# LimaIO.net
KiCad netlist of a schematic drawn in EAGLE
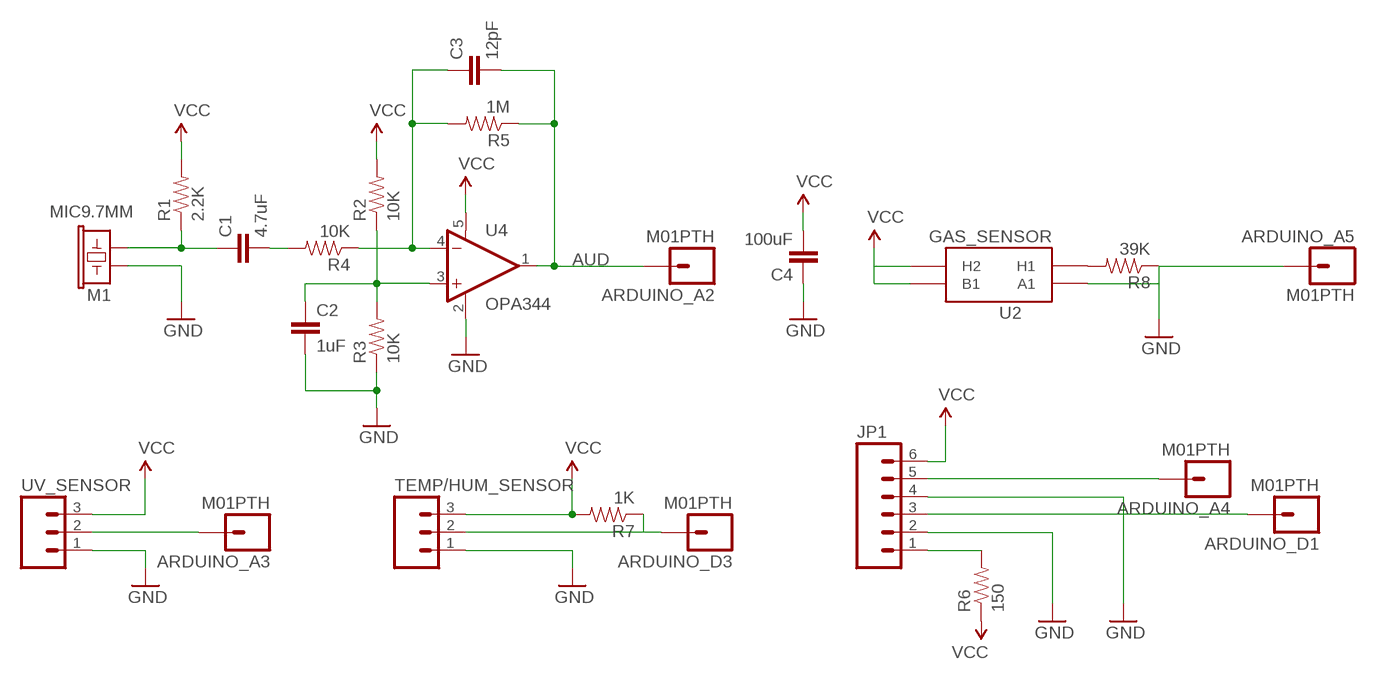
[diagram p0: schematic, sheet 1]

(export (version "E")
  (design (tool "Eeschema 10.0.6"))
  (components
    (comp (ref "ARDUINO_A2")
      (value "M01PTH")
      (footprint "eagle-import:1X01")
      (libsource (lib "eagle-import") (part "M01PTH"))
    )
    (comp (ref "ARDUINO_A3")
      (value "M01PTH")
      (footprint "eagle-import:1X01")
      (libsource (lib "eagle-import") (part "M01PTH"))
    )
    (comp (ref "ARDUINO_A4")
      (value "M01PTH")
      (footprint "eagle-import:1X01")
      (libsource (lib "eagle-import") (part "M01PTH"))
    )
    (comp (ref "ARDUINO_A5")
      (value "M01PTH")
      (footprint "eagle-import:1X01")
      (libsource (lib "eagle-import") (part "M01PTH"))
    )
    (comp (ref "ARDUINO_D1")
      (value "M01PTH")
      (footprint "eagle-import:1X01")
      (libsource (lib "eagle-import") (part "M01PTH"))
    )
    (comp (ref "ARDUINO_D3")
      (value "M01PTH")
      (footprint "eagle-import:1X01")
      (libsource (lib "eagle-import") (part "M01PTH"))
    )
    (comp (ref "C1")
      (value "4.7uF")
      (footprint "eagle-import:0402-CAP")
      (libsource (lib "eagle-import") (part "CAP0402-CAP"))
    )
    (comp (ref "C2")
      (value "1uF")
      (footprint "eagle-import:0402-CAP")
      (libsource (lib "eagle-import") (part "CAP0402-CAP"))
    )
    (comp (ref "C3")
      (value "12pF")
      (footprint "eagle-import:0402-CAP")
      (libsource (lib "eagle-import") (part "CAP0402-CAP"))
    )
    (comp (ref "C4")
      (value "100uF")
      (footprint "eagle-import:0402-CAP")
      (libsource (lib "eagle-import") (part "CAP0402-CAP"))
    )
    (comp (ref "JP1")
      (value "M06LONGPADS")
      (footprint "eagle-import:1X06_LONGPADS")
      (libsource (lib "eagle-import") (part "M06LONGPADS"))
    )
    (comp (ref "M1")
      (value "MIC9.7MM")
      (footprint "eagle-import:MIC-9.7MM")
      (libsource (lib "eagle-import") (part "MIC9.7MM"))
    )
    (comp (ref "R1")
      (value "2.2K")
      (footprint "eagle-import:0402-RES")
      (libsource (lib "eagle-import") (part "RESISTOR0402-RES"))
    )
    (comp (ref "R2")
      (value "10K")
      (footprint "eagle-import:0402-RES")
      (libsource (lib "eagle-import") (part "RESISTOR0402-RES"))
    )
    (comp (ref "R3")
      (value "10K")
      (footprint "eagle-import:0402-RES")
      (libsource (lib "eagle-import") (part "RESISTOR0402-RES"))
    )
    (comp (ref "R4")
      (value "10K")
      (footprint "eagle-import:0402-RES")
      (libsource (lib "eagle-import") (part "RESISTOR0402-RES"))
    )
    (comp (ref "R5")
      (value "1M")
      (footprint "eagle-import:0402-RES")
      (libsource (lib "eagle-import") (part "RESISTOR0402-RES"))
    )
    (comp (ref "R6")
      (value "150")
      (footprint "eagle-import:0402-RES")
      (libsource (lib "eagle-import") (part "RESISTOR0402-RES"))
    )
    (comp (ref "R7")
      (value "1K")
      (footprint "eagle-import:0402-RES")
      (libsource (lib "eagle-import") (part "RESISTOR0402-RES"))
    )
    (comp (ref "R8")
      (value "39K")
      (footprint "eagle-import:0402-RES")
      (libsource (lib "eagle-import") (part "RESISTOR0402-RES"))
    )
    (comp (ref "TEMP/HUM_SENSOR")
      (value "M03PTH")
      (footprint "eagle-import:1X03")
      (libsource (lib "eagle-import") (part "M03PTH"))
    )
    (comp (ref "U2")
      (value "GAS_SENSOR")
      (footprint "eagle-import:MQ-3")
      (libsource (lib "eagle-import") (part "GAS_SENSOR"))
    )
    (comp (ref "U4")
      (value "OPA344")
      (footprint "eagle-import:SOT23-5")
      (libsource (lib "eagle-import") (part "OPA344"))
    )
    (comp (ref "UV_SENSOR")
      (value "M03PTH")
      (footprint "eagle-import:1X03")
      (libsource (lib "eagle-import") (part "M03PTH"))
    )
  )
  (nets
    (net (code "1") (name "/AUD") (class "Default")
      (node (ref "ARDUINO_A2") (pin "1") (pinfunction "1_1") (pintype "passive"))
      (node (ref "C3") (pin "2") (pinfunction "2_2") (pintype "passive"))
      (node (ref "R5") (pin "1") (pinfunction "1_1") (pintype "passive"))
      (node (ref "U4") (pin "1") (pinfunction "OUT_1") (pintype "output"))
    )
    (net (code "2") (name "GND") (class "Default")
      (node (ref "ARDUINO_A5") (pin "1") (pinfunction "1_1") (pintype "passive"))
      (node (ref "C2") (pin "2") (pinfunction "2_2") (pintype "passive"))
      (node (ref "C4") (pin "1") (pinfunction "1_1") (pintype "passive"))
      (node (ref "JP1") (pin "2") (pinfunction "2_2") (pintype "passive"))
      (node (ref "JP1") (pin "4") (pinfunction "4_4") (pintype "passive"))
      (node (ref "M1") (pin "2") (pinfunction "2_2") (pintype "passive"))
      (node (ref "R3") (pin "1") (pinfunction "1_1") (pintype "passive"))
      (node (ref "R8") (pin "1") (pinfunction "1_1") (pintype "passive"))
      (node (ref "TEMP/HUM_SENSOR") (pin "1") (pinfunction "1_1") (pintype "passive"))
      (node (ref "U2") (pin "A1") (pinfunction "A1_A1") (pintype "bidirectional"))
      (node (ref "U4") (pin "2") (pinfunction "V-_2") (pintype "power_in"))
      (node (ref "UV_SENSOR") (pin "1") (pinfunction "1_1") (pintype "passive"))
    )
    (net (code "3") (name "Net-(ARDUINO_A3-Pad1)") (class "Default")
      (node (ref "ARDUINO_A3") (pin "1") (pinfunction "1_1") (pintype "passive"))
      (node (ref "UV_SENSOR") (pin "2") (pinfunction "2_2") (pintype "passive"))
    )
    (net (code "4") (name "Net-(ARDUINO_A4-Pad1)") (class "Default")
      (node (ref "ARDUINO_A4") (pin "1") (pinfunction "1_1") (pintype "passive"))
      (node (ref "JP1") (pin "5") (pinfunction "5_5") (pintype "passive"))
    )
    (net (code "5") (name "Net-(ARDUINO_D1-Pad1)") (class "Default")
      (node (ref "ARDUINO_D1") (pin "1") (pinfunction "1_1") (pintype "passive"))
      (node (ref "JP1") (pin "3") (pinfunction "3_3") (pintype "passive"))
    )
    (net (code "6") (name "Net-(ARDUINO_D3-Pad1)") (class "Default")
      (node (ref "ARDUINO_D3") (pin "1") (pinfunction "1_1") (pintype "passive"))
      (node (ref "R7") (pin "1") (pinfunction "1_1") (pintype "passive"))
      (node (ref "TEMP/HUM_SENSOR") (pin "2") (pinfunction "2_2") (pintype "passive"))
    )
    (net (code "7") (name "Net-(C1-Pad1)") (class "Default")
      (node (ref "C1") (pin "1") (pinfunction "1_1") (pintype "passive"))
      (node (ref "M1") (pin "1") (pinfunction "1_1") (pintype "passive"))
      (node (ref "R1") (pin "1") (pinfunction "1_1") (pintype "passive"))
    )
    (net (code "8") (name "Net-(C1-Pad2)") (class "Default")
      (node (ref "C1") (pin "2") (pinfunction "2_2") (pintype "passive"))
      (node (ref "R4") (pin "2") (pinfunction "2_2") (pintype "passive"))
    )
    (net (code "9") (name "Net-(JP1-Pad1)") (class "Default")
      (node (ref "JP1") (pin "1") (pinfunction "1_1") (pintype "passive"))
      (node (ref "R6") (pin "2") (pinfunction "2_2") (pintype "passive"))
    )
    (net (code "10") (name "Net-(U2-H1)") (class "Default")
      (node (ref "R8") (pin "2") (pinfunction "2_2") (pintype "passive"))
      (node (ref "U2") (pin "HA") (pinfunction "H1_HA") (pintype "bidirectional"))
    )
    (net (code "11") (name "Net-(U4-+IN)") (class "Default")
      (node (ref "C2") (pin "1") (pinfunction "1_1") (pintype "passive"))
      (node (ref "R2") (pin "1") (pinfunction "1_1") (pintype "passive"))
      (node (ref "R3") (pin "2") (pinfunction "2_2") (pintype "passive"))
      (node (ref "U4") (pin "3") (pinfunction "+IN_3") (pintype "input"))
    )
    (net (code "12") (name "Net-(U4--IN)") (class "Default")
      (node (ref "C3") (pin "1") (pinfunction "1_1") (pintype "passive"))
      (node (ref "R4") (pin "1") (pinfunction "1_1") (pintype "passive"))
      (node (ref "R5") (pin "2") (pinfunction "2_2") (pintype "passive"))
      (node (ref "U4") (pin "4") (pinfunction "-IN_4") (pintype "input"))
    )
    (net (code "13") (name "VCC") (class "Default")
      (node (ref "C4") (pin "2") (pinfunction "2_2") (pintype "passive"))
      (node (ref "JP1") (pin "6") (pinfunction "6_6") (pintype "passive"))
      (node (ref "R1") (pin "2") (pinfunction "2_2") (pintype "passive"))
      (node (ref "R2") (pin "2") (pinfunction "2_2") (pintype "passive"))
      (node (ref "R6") (pin "1") (pinfunction "1_1") (pintype "passive"))
      (node (ref "R7") (pin "2") (pinfunction "2_2") (pintype "passive"))
      (node (ref "TEMP/HUM_SENSOR") (pin "3") (pinfunction "3_3") (pintype "passive"))
      (node (ref "U2") (pin "B1") (pinfunction "B1_B1") (pintype "bidirectional"))
      (node (ref "U2") (pin "HB") (pinfunction "H2_HB") (pintype "bidirectional"))
      (node (ref "U4") (pin "5") (pinfunction "V+_5") (pintype "power_in"))
      (node (ref "UV_SENSOR") (pin "3") (pinfunction "3_3") (pintype "passive"))
    )
  )
)
